# boost_converter_pcb_design.net
KiCad netlist of a schematic drawn in Altium Designer
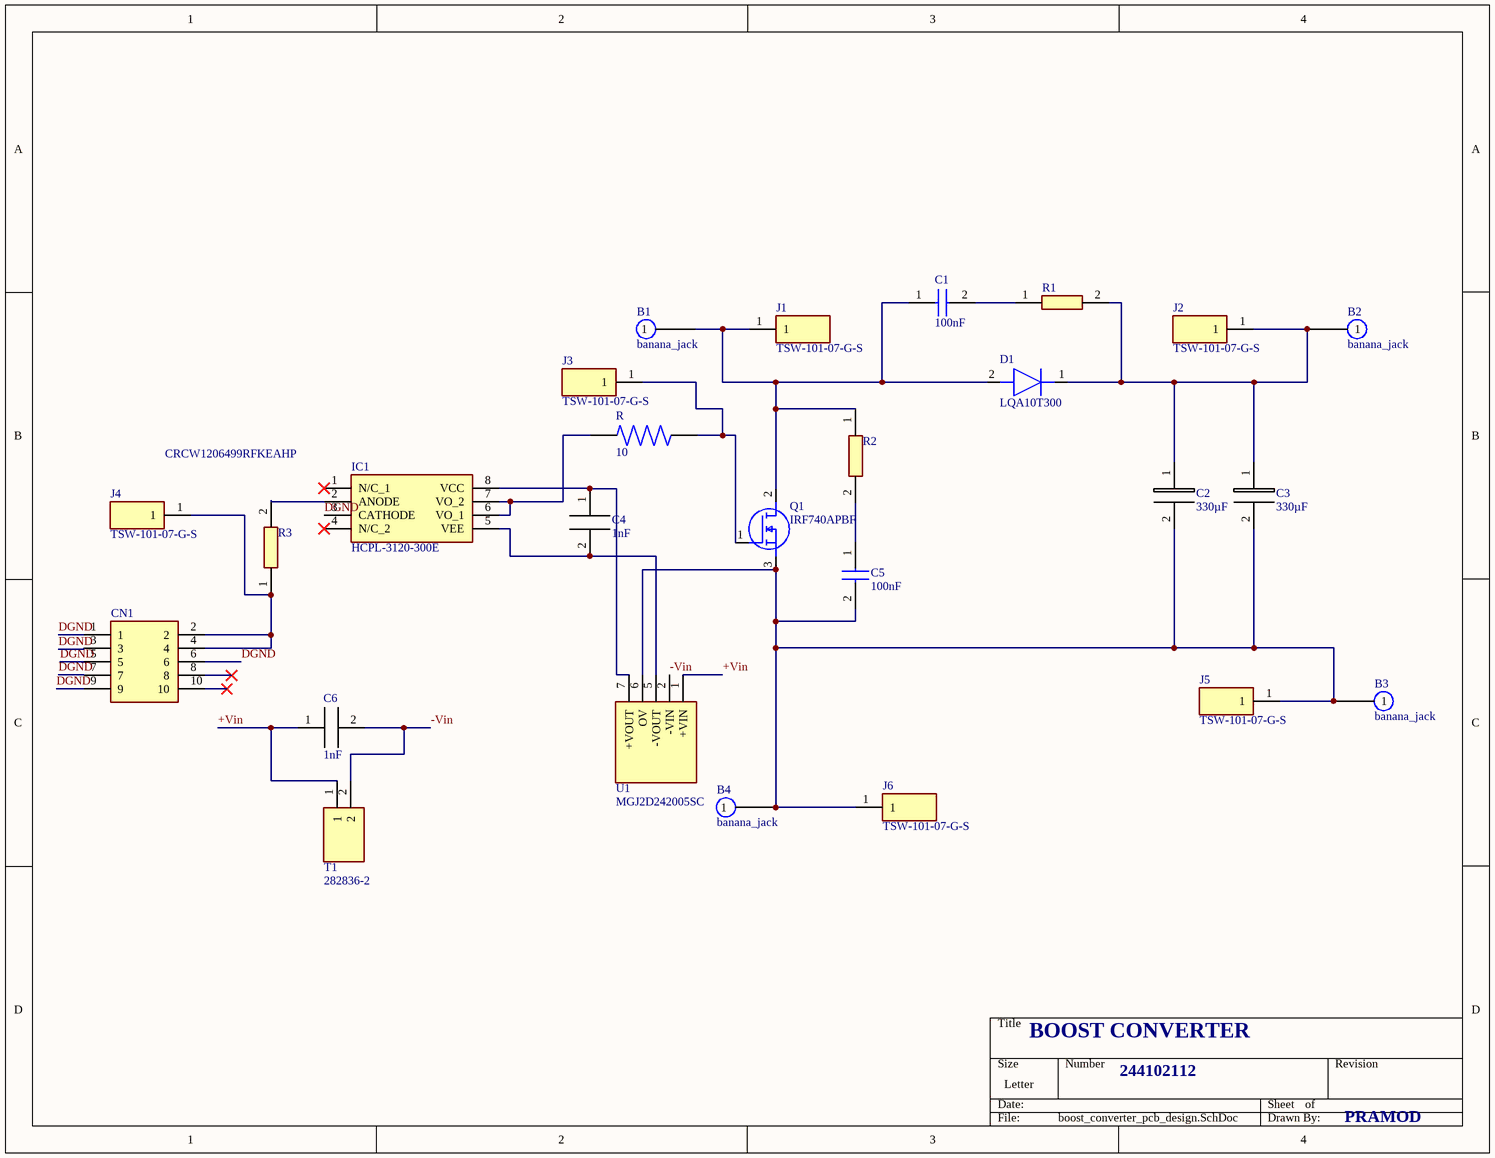
[diagram p0: boost_converter_pcb_design.SchDoc]

(export (version "E")
  (design (tool "Eeschema 10.0.6"))
  (components
    (comp (ref "B1")
      (value "banana_jack")
      (footprint "banana_connector")
      (libsource (lib "V Pramod") (part "banana_jack"))
    )
    (comp (ref "B2")
      (value "banana_jack")
      (footprint "banana_connector")
      (libsource (lib "V Pramod") (part "banana_jack"))
    )
    (comp (ref "B3")
      (value "banana_jack")
      (footprint "banana_connector")
      (libsource (lib "V Pramod") (part "banana_jack"))
    )
    (comp (ref "B4")
      (value "banana_jack")
      (footprint "banana_connector")
      (libsource (lib "V Pramod") (part "banana_jack"))
    )
    (comp (ref "C1")
      (value "100nF")
      (footprint "C1206")
      (description "Multilayer Ceramic \r\nCapacitors MLCC - \r\nSMD/SMT 50V \r\n0.1uF X7R 1206 \r\n10%")
      (fields
        (field (name "MOUSER PART NUMBER") "80-C1206C104K5R")
        (field (name "ARROW PART NUMBER") "C1206C104K5RACTU")
      )
      (libsource (lib "V Pramod") (part "MKP1V011004B00JSSD"))
    )
    (comp (ref "C2")
      (value "330µF")
      (footprint "CAP_B43641A9108M057")
      (description "Electrolytic Capacitor, 330 µF, 550 V, ± 20%, Snap-In, 5000 hours @ 85°C")
      (fields (field (name "Comment") "B43541A7337M000"))
      (libsource (lib "V Pramod") (part "B43541A7337M000"))
    )
    (comp (ref "C3")
      (value "330µF")
      (footprint "CAP_B43641A9108M057")
      (description "Electrolytic Capacitor, 330 µF, 550 V, ± 20%, Snap-In, 5000 hours @ 85°C")
      (fields (field (name "Comment") "B43541A7337M000"))
      (libsource (lib "V Pramod") (part "B43541A7337M000"))
    )
    (comp (ref "C4")
      (value "1nF")
      (footprint "B32652_(18_x_5)")
      (fields (field (name "MANUFACTURER_PART_NUMBER") "B32652A2102J000"))
      (libsource (lib "V Pramod") (part "B32652A2102J000"))
    )
    (comp (ref "C5")
      (value "100nF")
      (footprint "C1206")
      (description "Multilayer Ceramic \r\nCapacitors MLCC - \r\nSMD/SMT 50V \r\n0.1uF X7R 1206 \r\n10%")
      (fields
        (field (name "MOUSER PART NUMBER") "80-C1206C104K5R")
        (field (name "ARROW PART NUMBER") "C1206C104K5RACTU")
      )
      (libsource (lib "V Pramod") (part "MKP1V011004B00JSSD"))
    )
    (comp (ref "C6")
      (value "1nF")
      (footprint "B32652_(18_x_5)")
      (fields (field (name "MANUFACTURER_PART_NUMBER") "B32652A2102J000"))
      (libsource (lib "V Pramod") (part "B32652A2102J000"))
    )
    (comp (ref "CN1")
      (value "30310-6002HB")
      (footprint "SHDR10W64P254_2X5_2030X878X930P")
      (description "Connector")
      (fields (field (name "MOUSER PART NUMBER") "517-30310-6002"))
      (libsource (lib "V Pramod") (part "30310-6002HB"))
    )
    (comp (ref "D1")
      (value "LQA10T300")
      (footprint "TO508P470X1016X2215-2P")
      (description "Diode")
      (fields (field (name "MOUSER PART NUMBER") "903-LQA10T300"))
      (libsource (lib "V Pramod") (part "LQA30T300"))
    )
    (comp (ref "IC1")
      (value "HCPL-3120-300E")
      (footprint "HCPL-3120-GULL-WING")
      (description "Integrated Circuit")
      (fields (field (name "MOUSER PART NUMBER") "630-HCPL-3120-300E"))
      (libsource (lib "V Pramod") (part "HCPL-3120-300E"))
    )
    (comp (ref "J1")
      (value "TSW-101-07-G-S")
      (footprint "TSW-101-XX-YY-S")
      (description "Connector")
      (fields (field (name "MOUSER PART NUMBER") "200-TSW10107GS"))
      (libsource (lib "") (part "TSW-101-07-G-S_1"))
    )
    (comp (ref "J2")
      (value "TSW-101-07-G-S")
      (footprint "TSW-101-XX-YY-S")
      (description "Connector")
      (fields (field (name "MOUSER PART NUMBER") "200-TSW10107GS"))
      (libsource (lib "V Pramod") (part "TSW-101-07-G-S"))
    )
    (comp (ref "J3")
      (value "TSW-101-07-G-S")
      (footprint "TSW-101-XX-YY-S")
      (description "Connector")
      (fields (field (name "MOUSER PART NUMBER") "200-TSW10107GS"))
      (libsource (lib "V Pramod") (part "TSW-101-07-G-S"))
    )
    (comp (ref "J4")
      (value "TSW-101-07-G-S")
      (footprint "TSW-101-XX-YY-S")
      (description "Connector")
      (fields (field (name "MOUSER PART NUMBER") "200-TSW10107GS"))
      (libsource (lib "V Pramod") (part "TSW-101-07-G-S"))
    )
    (comp (ref "J5")
      (value "TSW-101-07-G-S")
      (footprint "TSW-101-XX-YY-S")
      (description "Connector")
      (fields (field (name "MOUSER PART NUMBER") "200-TSW10107GS"))
      (libsource (lib "V Pramod") (part "TSW-101-07-G-S"))
    )
    (comp (ref "J6")
      (value "TSW-101-07-G-S")
      (footprint "TSW-101-XX-YY-S")
      (description "Connector")
      (fields (field (name "MOUSER PART NUMBER") "200-TSW10107GS"))
      (libsource (lib "") (part "TSW-101-07-G-S_1"))
    )
    (comp (ref "Q1")
      (value "IRF740APBF")
      (footprint "TO254P465X1024X2050-3P")
      (description "MOSFET (N-Channel)")
      (fields (field (name "MOUSER PART NUMBER") "844-IRF740APBF"))
      (libsource (lib "V Pramod") (part "IRF740APBF"))
    )
    (comp (ref "R")
      (value "10")
      (footprint "RESC2012X60N")
      (fields (field (name "MP") "CRCW080510R0FKEAHP") (field (name "MF") "Vishay"))
      (libsource (lib "V Pramod") (part "CRCW080510R0FKEAHP"))
    )
    (comp (ref "R1")
      (value "355010RFT")
      (footprint "RESC11050X120N")
      (description "Resistor")
      (fields (field (name "MOUSER PART NUMBER") "279-355010RFT"))
      (libsource (lib "") (part "CMP2010AFX-1003ELF_1"))
    )
    (comp (ref "R2")
      (value "355010RFT")
      (footprint "RESC11050X120N")
      (description "Resistor")
      (fields (field (name "MOUSER PART NUMBER") "279-355010RFT"))
      (libsource (lib "V Pramod") (part "CMP2010AFX-1003ELF"))
    )
    (comp (ref "R3")
      (value "CRCW1206499RFKEAHP")
      (footprint "SamacSys:RESC3116X65N")
      (description "Resistor")
      (fields (field (name "MOUSER PART NUMBER") "71-CRCW1206499RFKEAH"))
      (libsource (lib "*") (part "CRCW1206499RFKEAHP"))
    )
    (comp (ref "T1")
      (value "282836-2")
      (footprint "2828362")
      (description "Connector")
      (fields (field (name "MOUSER PART NUMBER") "571-2828362"))
      (libsource (lib "V Pramod") (part "282836-2"))
    )
    (comp (ref "U1")
      (value "MGJ2D242005SC")
      (footprint "MURATA-MGJ2")
      (description "Undefined or Miscellaneous")
      (fields (field (name "MOUSER PART NUMBER") "580-MGJ2D242005SC"))
      (libsource (lib "V Pramod") (part "MGJ2D242005SC"))
    )
  )
  (nets
    (net (code "1") (name "/+Vin") (class "Default")
      (node (ref "C6") (pin "1") (pinfunction "1_1") (pintype "passive"))
      (node (ref "T1") (pin "1") (pinfunction "1_1") (pintype "passive"))
      (node (ref "U1") (pin "1") (pinfunction "+VIN_1") (pintype "passive"))
    )
    (net (code "2") (name "/-Vin") (class "Default")
      (node (ref "C6") (pin "2") (pinfunction "2_2") (pintype "passive"))
      (node (ref "T1") (pin "2") (pinfunction "2_2") (pintype "passive"))
      (node (ref "U1") (pin "2") (pinfunction "-VIN_2") (pintype "passive"))
    )
    (net (code "3") (name "/DGND") (class "Default")
      (node (ref "CN1") (pin "1") (pinfunction "1_1") (pintype "passive"))
      (node (ref "CN1") (pin "3") (pinfunction "3_3") (pintype "passive"))
      (node (ref "CN1") (pin "5") (pinfunction "5_5") (pintype "passive"))
      (node (ref "CN1") (pin "6") (pinfunction "6_6") (pintype "passive"))
      (node (ref "CN1") (pin "7") (pinfunction "7_7") (pintype "passive"))
      (node (ref "CN1") (pin "9") (pinfunction "9_9") (pintype "passive"))
      (node (ref "IC1") (pin "3") (pinfunction "CATHODE_3") (pintype "passive"))
    )
    (net (code "4") (name "Net-(B1-1)") (class "Default")
      (node (ref "B1") (pin "B?") (pinfunction "1_B?") (pintype "passive"))
      (node (ref "C1") (pin "1") (pinfunction "1_1") (pintype "passive"))
      (node (ref "D1") (pin "2") (pinfunction "A_2") (pintype "passive"))
      (node (ref "J1") (pin "1") (pinfunction "1_1") (pintype "passive"))
      (node (ref "Q1") (pin "2") (pinfunction "D_2") (pintype "passive"))
      (node (ref "R2") (pin "1") (pinfunction "1_1") (pintype "passive"))
    )
    (net (code "5") (name "Net-(B2-1)") (class "Default")
      (node (ref "B2") (pin "B?") (pinfunction "1_B?") (pintype "passive"))
      (node (ref "C2") (pin "1") (pinfunction "1_1") (pintype "passive"))
      (node (ref "C3") (pin "1") (pinfunction "1_1") (pintype "passive"))
      (node (ref "D1") (pin "1") (pinfunction "K_1") (pintype "passive"))
      (node (ref "J2") (pin "1") (pinfunction "1_1") (pintype "passive"))
      (node (ref "R1") (pin "2") (pinfunction "2_2") (pintype "passive"))
    )
    (net (code "6") (name "Net-(B3-1)") (class "Default")
      (node (ref "B3") (pin "B?") (pinfunction "1_B?") (pintype "passive"))
      (node (ref "B4") (pin "B?") (pinfunction "1_B?") (pintype "passive"))
      (node (ref "C2") (pin "2") (pinfunction "2_2") (pintype "passive"))
      (node (ref "C3") (pin "2") (pinfunction "2_2") (pintype "passive"))
      (node (ref "C5") (pin "2") (pinfunction "2_2") (pintype "passive"))
      (node (ref "J5") (pin "1") (pinfunction "1_1") (pintype "passive"))
      (node (ref "J6") (pin "1") (pinfunction "1_1") (pintype "passive"))
      (node (ref "Q1") (pin "3") (pinfunction "S_3") (pintype "passive"))
      (node (ref "U1") (pin "6") (pinfunction "OV_6") (pintype "passive"))
    )
    (net (code "7") (name "Net-(C1-Pad2)") (class "Default")
      (node (ref "C1") (pin "2") (pinfunction "2_2") (pintype "passive"))
      (node (ref "R1") (pin "1") (pinfunction "1_1") (pintype "passive"))
    )
    (net (code "8") (name "Net-(C5-Pad1)") (class "Default")
      (node (ref "C5") (pin "1") (pinfunction "1_1") (pintype "passive"))
      (node (ref "R2") (pin "2") (pinfunction "2_2") (pintype "passive"))
    )
    (net (code "9") (name "Net-(CN1-Pad2)") (class "Default")
      (node (ref "CN1") (pin "2") (pinfunction "2_2") (pintype "passive"))
      (node (ref "CN1") (pin "4") (pinfunction "4_4") (pintype "passive"))
      (node (ref "J4") (pin "1") (pinfunction "1_1") (pintype "passive"))
      (node (ref "R3") (pin "1") (pinfunction "1_1") (pintype "passive"))
    )
    (net (code "10") (name "Net-(IC1-ANODE)") (class "Default")
      (node (ref "IC1") (pin "2") (pinfunction "ANODE_2") (pintype "passive"))
      (node (ref "R3") (pin "2") (pinfunction "2_2") (pintype "passive"))
    )
    (net (code "11") (name "Net-(IC1-VCC)") (class "Default")
      (node (ref "C4") (pin "1") (pinfunction "1_1") (pintype "passive"))
      (node (ref "IC1") (pin "8") (pinfunction "VCC_8") (pintype "passive"))
      (node (ref "U1") (pin "7") (pinfunction "+VOUT_7") (pintype "passive"))
    )
    (net (code "12") (name "Net-(IC1-VEE)") (class "Default")
      (node (ref "C4") (pin "2") (pinfunction "2_2") (pintype "passive"))
      (node (ref "IC1") (pin "5") (pinfunction "VEE_5") (pintype "passive"))
      (node (ref "U1") (pin "5") (pinfunction "-VOUT_5") (pintype "passive"))
    )
    (net (code "13") (name "Net-(IC1-VO_1)") (class "Default")
      (node (ref "IC1") (pin "6") (pinfunction "VO_1_6") (pintype "passive"))
      (node (ref "IC1") (pin "7") (pinfunction "VO_2_7") (pintype "passive"))
      (node (ref "R") (pin "1") (pinfunction "1_1") (pintype "passive"))
    )
    (net (code "14") (name "Net-(Q1-G)") (class "Default")
      (node (ref "J3") (pin "1") (pinfunction "1_1") (pintype "passive"))
      (node (ref "Q1") (pin "1") (pinfunction "G_1") (pintype "passive"))
      (node (ref "R") (pin "2") (pinfunction "2_2") (pintype "passive"))
    )
    (net (code "15") (name "unconnected-(CN1-Pad8)") (class "Default")
      (node (ref "CN1") (pin "8") (pinfunction "8_8") (pintype "passive+no_connect"))
    )
    (net (code "16") (name "unconnected-(CN1-Pad10)") (class "Default")
      (node (ref "CN1") (pin "10") (pinfunction "10_10") (pintype "passive+no_connect"))
    )
    (net (code "17") (name "unconnected-(IC1-N{slash}C_1-Pad1)") (class "Default")
      (node (ref "IC1") (pin "1") (pinfunction "N/C_1_1") (pintype "passive+no_connect"))
    )
    (net (code "18") (name "unconnected-(IC1-N{slash}C_2-Pad4)") (class "Default")
      (node (ref "IC1") (pin "4") (pinfunction "N/C_2_4") (pintype "passive+no_connect"))
    )
  )
)
